# blinky_skull.net
KiCad netlist of a schematic drawn in EAGLE
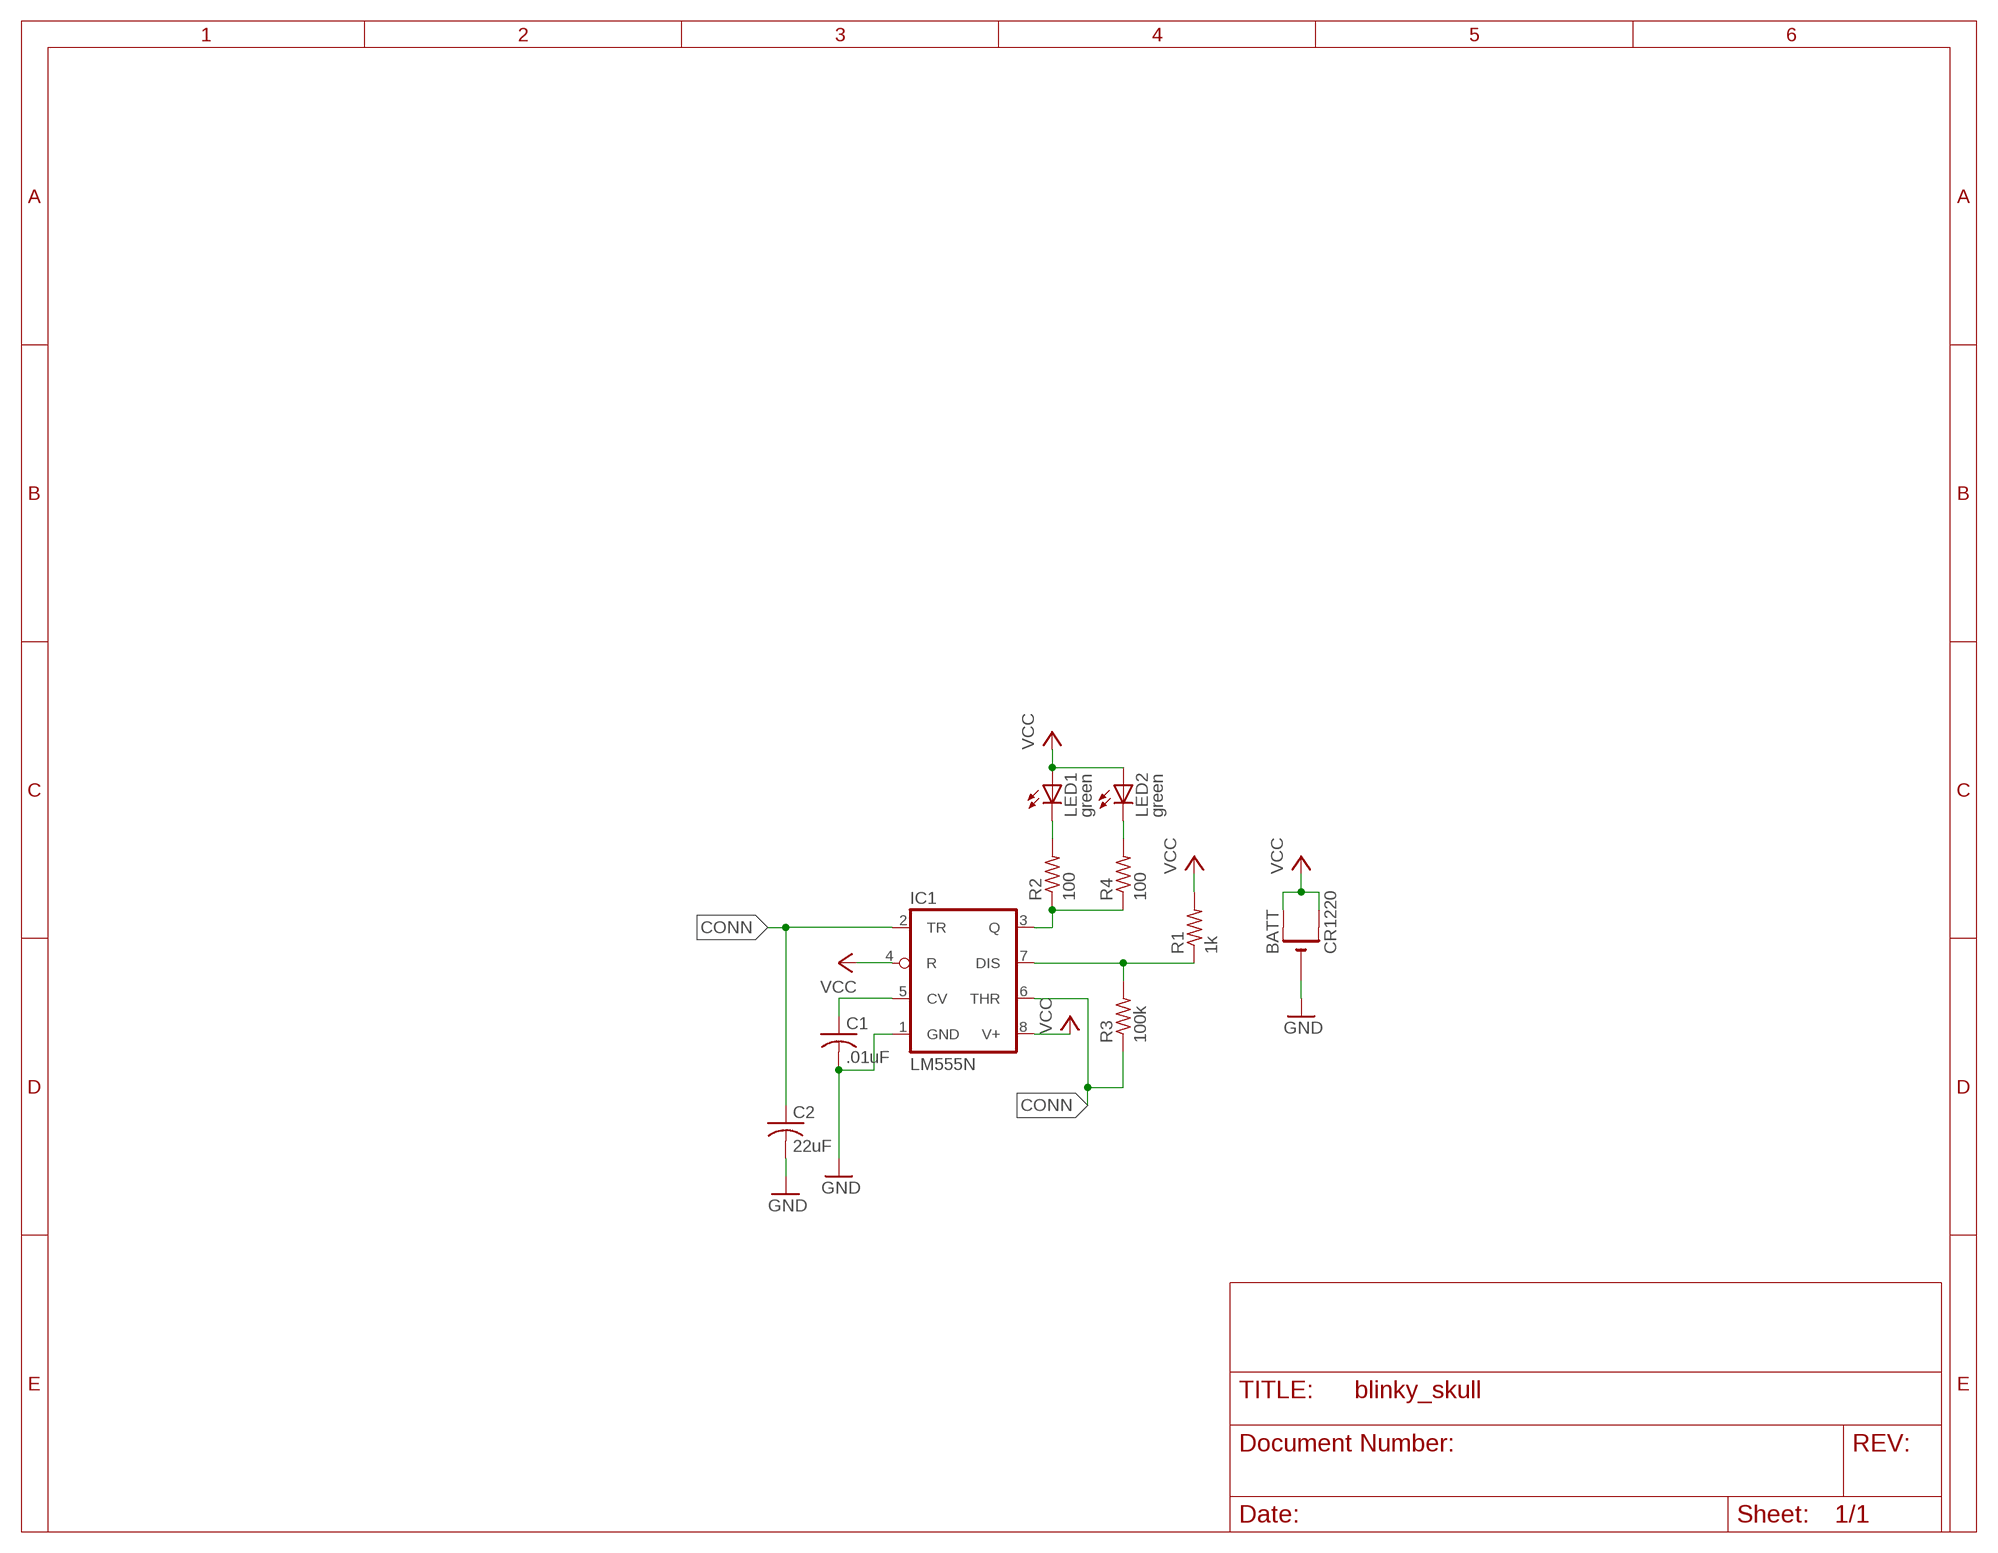
[diagram p0: schematic, sheet 1]

(export (version "E")
  (design (tool "Eeschema 10.0.6"))
  (components
    (comp (ref "BATT")
      (value "CR1220")
      (footprint "eagle-import:CR1220-SMD")
      (libsource (lib "eagle-import") (part "CR1220SMT"))
    )
    (comp (ref "C1")
      (value ".01uF")
      (footprint "eagle-import:C0805")
      (libsource (lib "eagle-import") (part "C-USC0805"))
    )
    (comp (ref "C2")
      (value "22uF")
      (footprint "eagle-import:C0805")
      (libsource (lib "eagle-import") (part "C-USC0805"))
    )
    (comp (ref "IC1")
      (value "LM555N")
      (footprint "eagle-import:DIL08-ROUND")
      (libsource (lib "eagle-import") (part "555NLM"))
    )
    (comp (ref "LED1")
      (value "green")
      (footprint "eagle-import:LED5MM")
      (libsource (lib "eagle-import") (part "LED5MM"))
    )
    (comp (ref "LED2")
      (value "green")
      (footprint "eagle-import:LED5MM")
      (libsource (lib "eagle-import") (part "LED5MM"))
    )
    (comp (ref "R1")
      (value "1k")
      (footprint "eagle-import:R0805")
      (libsource (lib "eagle-import") (part "R-US_R0805"))
    )
    (comp (ref "R2")
      (value "100")
      (footprint "eagle-import:R0805")
      (libsource (lib "eagle-import") (part "R-US_R0805"))
    )
    (comp (ref "R3")
      (value "100k")
      (footprint "eagle-import:R0805")
      (libsource (lib "eagle-import") (part "R-US_R0805"))
    )
    (comp (ref "R4")
      (value "100")
      (footprint "eagle-import:R0805")
      (libsource (lib "eagle-import") (part "R-US_R0805"))
    )
  )
  (nets
    (net (code "1") (name "CONN") (class "Default")
      (node (ref "C2") (pin "1") (pinfunction "1_1") (pintype "passive"))
      (node (ref "IC1") (pin "2") (pinfunction "TR_2") (pintype "input"))
      (node (ref "IC1") (pin "6") (pinfunction "THR_6") (pintype "input"))
      (node (ref "R3") (pin "1") (pinfunction "1_1") (pintype "passive"))
    )
    (net (code "2") (name "GND") (class "Default")
      (node (ref "BATT") (pin "-") (pinfunction "-_-") (pintype "passive"))
      (node (ref "C1") (pin "2") (pinfunction "2_2") (pintype "passive"))
      (node (ref "C2") (pin "2") (pinfunction "2_2") (pintype "passive"))
      (node (ref "IC1") (pin "1") (pinfunction "GND_1") (pintype "power_in"))
    )
    (net (code "3") (name "Net-(IC1-CV)") (class "Default")
      (node (ref "C1") (pin "1") (pinfunction "1_1") (pintype "passive"))
      (node (ref "IC1") (pin "5") (pinfunction "CV_5") (pintype "input"))
    )
    (net (code "4") (name "Net-(IC1-DIS)") (class "Default")
      (node (ref "IC1") (pin "7") (pinfunction "DIS_7") (pintype "input"))
      (node (ref "R1") (pin "1") (pinfunction "1_1") (pintype "passive"))
      (node (ref "R3") (pin "2") (pinfunction "2_2") (pintype "passive"))
    )
    (net (code "5") (name "Net-(IC1-Q)") (class "Default")
      (node (ref "IC1") (pin "3") (pinfunction "Q_3") (pintype "output"))
      (node (ref "R2") (pin "1") (pinfunction "1_1") (pintype "passive"))
      (node (ref "R4") (pin "1") (pinfunction "1_1") (pintype "passive"))
    )
    (net (code "6") (name "Net-(LED1-C)") (class "Default")
      (node (ref "LED1") (pin "K") (pinfunction "C_K") (pintype "passive"))
      (node (ref "R2") (pin "2") (pinfunction "2_2") (pintype "passive"))
    )
    (net (code "7") (name "Net-(LED2-C)") (class "Default")
      (node (ref "LED2") (pin "K") (pinfunction "C_K") (pintype "passive"))
      (node (ref "R4") (pin "2") (pinfunction "2_2") (pintype "passive"))
    )
    (net (code "8") (name "VCC") (class "Default")
      (node (ref "BATT") (pin "+$1") (pinfunction "+_+$1") (pintype "passive"))
      (node (ref "BATT") (pin "+$2") (pinfunction "+1_+$2") (pintype "passive"))
      (node (ref "IC1") (pin "4") (pinfunction "R_4") (pintype "input"))
      (node (ref "IC1") (pin "8") (pinfunction "V+_8") (pintype "power_in"))
      (node (ref "LED1") (pin "A") (pinfunction "A_A") (pintype "passive"))
      (node (ref "LED2") (pin "A") (pinfunction "A_A") (pintype "passive"))
      (node (ref "R1") (pin "2") (pinfunction "2_2") (pintype "passive"))
    )
  )
)
